# BreakOut-8x8-rev2.net
KiCad netlist of a schematic drawn in EAGLE
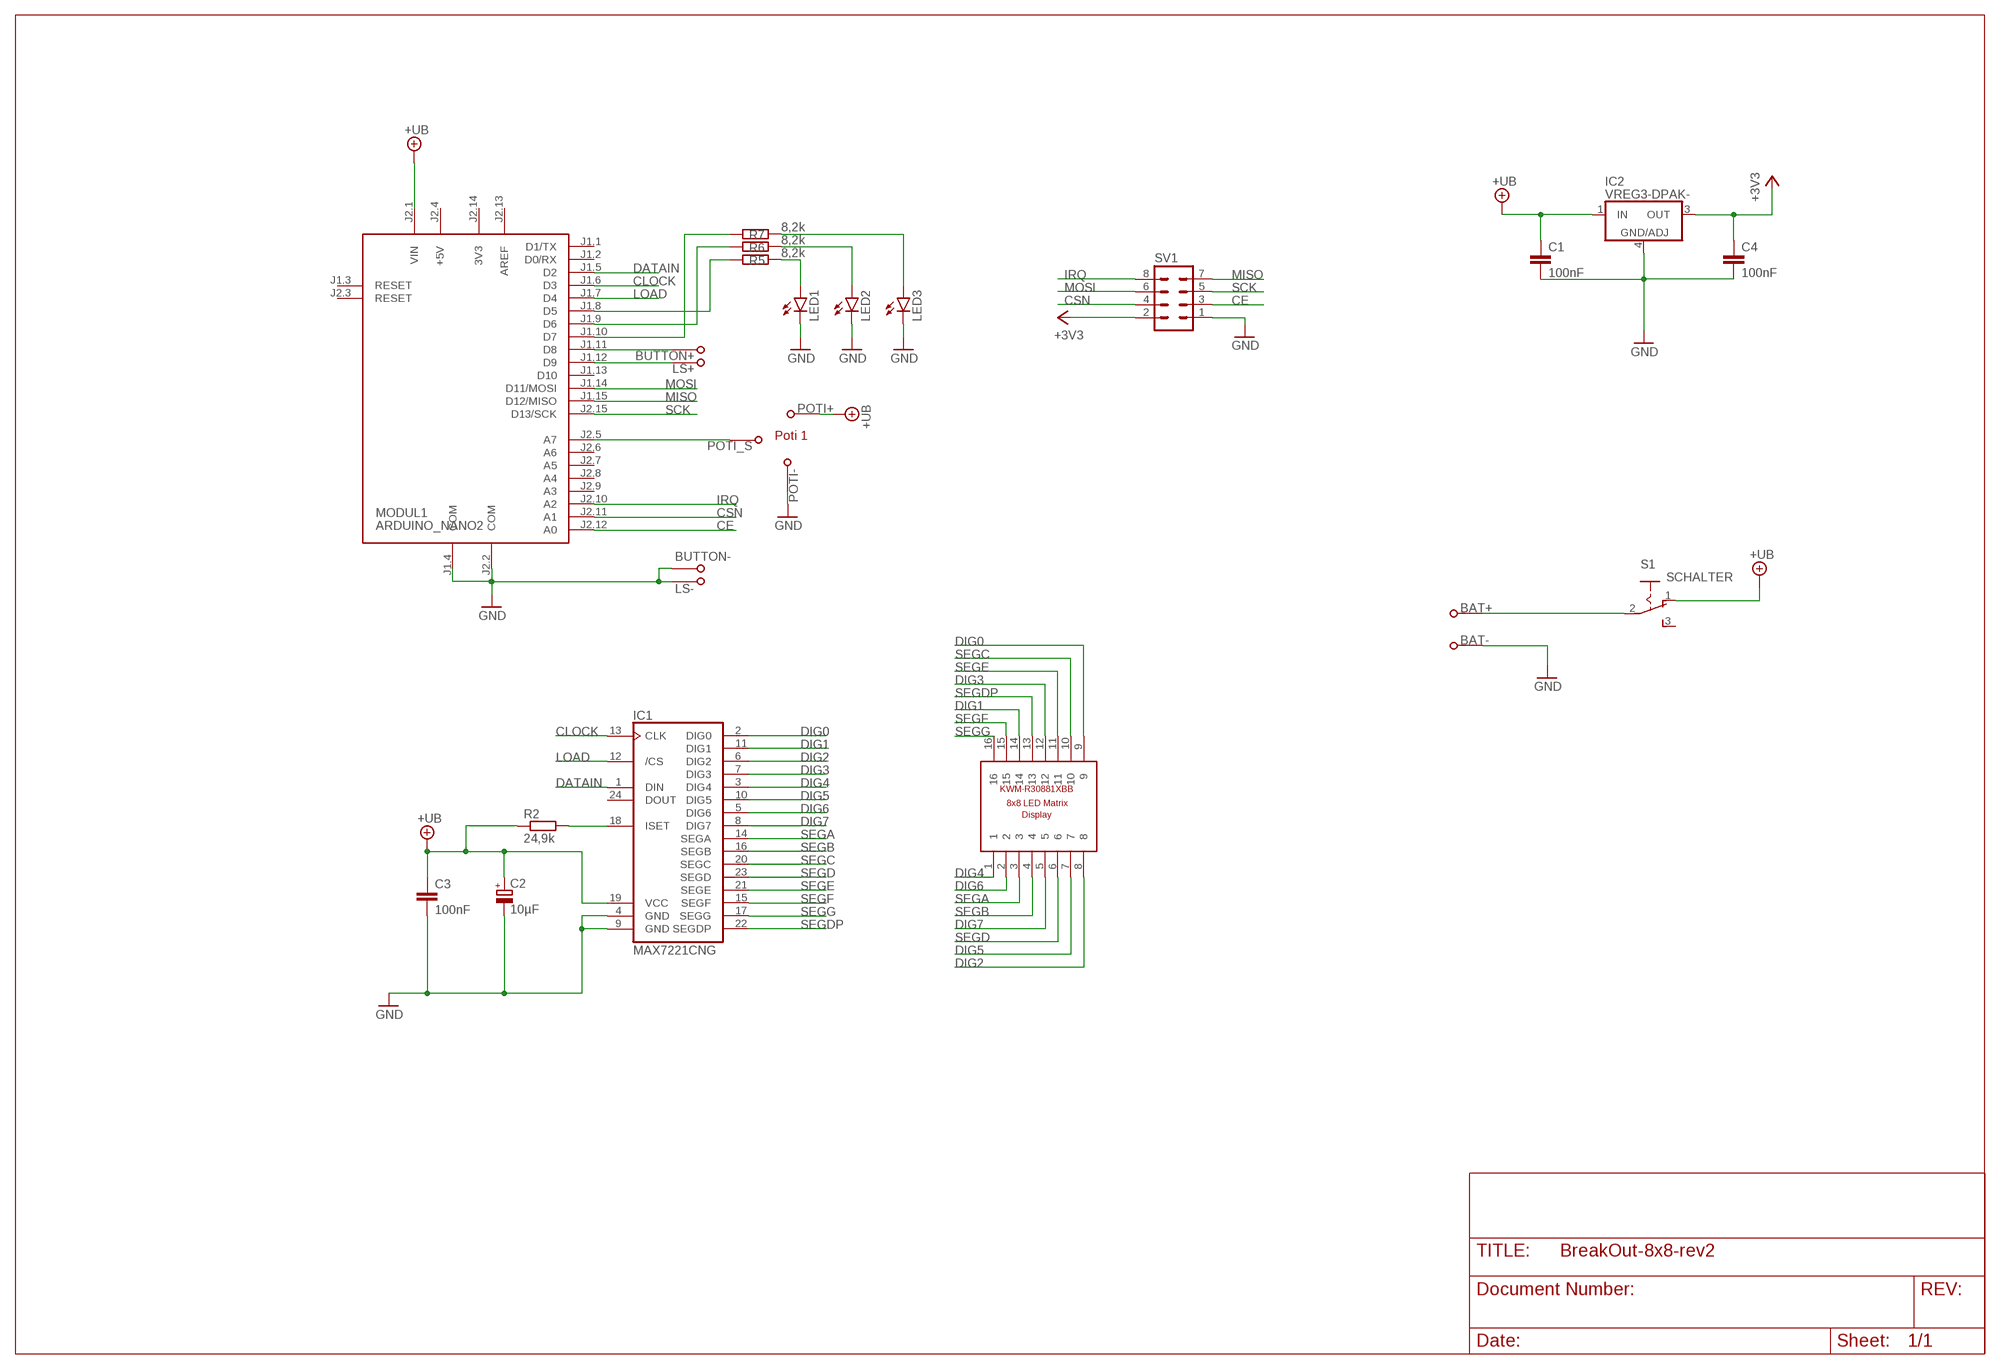
[diagram p0: schematic, sheet 1]

(export (version "E")
  (design (tool "Eeschema 10.0.6"))
  (components
    (comp (ref "BAT+")
      (value "PAD-NVSMD-2X3")
      (footprint "eagle-import:PAD-SO-2X3")
      (libsource (lib "eagle-import") (part "PAD-NVSMD-2X3"))
    )
    (comp (ref "BAT-")
      (value "PAD-NVSMD-2X3")
      (footprint "eagle-import:PAD-SO-2X3")
      (libsource (lib "eagle-import") (part "PAD-NVSMD-2X3"))
    )
    (comp (ref "BUTTON+")
      (value "PAD-NVSMD-2X3")
      (footprint "eagle-import:PAD-SO-2X3")
      (libsource (lib "eagle-import") (part "PAD-NVSMD-2X3"))
    )
    (comp (ref "BUTTON-")
      (value "PAD-NVSMD-2X3")
      (footprint "eagle-import:PAD-SO-2X3")
      (libsource (lib "eagle-import") (part "PAD-NVSMD-2X3"))
    )
    (comp (ref "C1")
      (value "100nF")
      (footprint "eagle-import:C0805")
      (libsource (lib "eagle-import") (part "C-EUC0805"))
    )
    (comp (ref "C2")
      (value "10µF")
      (footprint "eagle-import:C_6032-28R")
      (libsource (lib "eagle-import") (part "CPOL-EUC/6032-28R"))
    )
    (comp (ref "C3")
      (value "100nF")
      (footprint "eagle-import:C0805")
      (libsource (lib "eagle-import") (part "C-EUC0805"))
    )
    (comp (ref "C4")
      (value "100nF")
      (footprint "eagle-import:C0805")
      (libsource (lib "eagle-import") (part "C-EUC0805"))
    )
    (comp (ref "IC1")
      (value "MAX7221CNG")
      (footprint "eagle-import:DIL24-3")
      (libsource (lib "eagle-import") (part "MAX7221NGC"))
    )
    (comp (ref "IC2")
      (value "VREG3-DPAK-")
      (footprint "eagle-import:DPAK")
      (libsource (lib "eagle-import") (part "VREG3-?-DPAK"))
    )
    (comp (ref "LED1")
      (value "LED5MM")
      (footprint "eagle-import:LED5MM")
      (libsource (lib "eagle-import") (part "LED5MM"))
    )
    (comp (ref "LED2")
      (value "LED5MM")
      (footprint "eagle-import:LED5MM")
      (libsource (lib "eagle-import") (part "LED5MM"))
    )
    (comp (ref "LED3")
      (value "LED5MM")
      (footprint "eagle-import:LED5MM")
      (libsource (lib "eagle-import") (part "LED5MM"))
    )
    (comp (ref "LS+")
      (value "PAD-NVSMD-2X3")
      (footprint "eagle-import:PAD-SO-2X3")
      (libsource (lib "eagle-import") (part "PAD-NVSMD-2X3"))
    )
    (comp (ref "LS-")
      (value "PAD-NVSMD-2X3")
      (footprint "eagle-import:PAD-SO-2X3")
      (libsource (lib "eagle-import") (part "PAD-NVSMD-2X3"))
    )
    (comp (ref "MODUL1")
      (value "ARDUINO_NANO2")
      (footprint "eagle-import:ARDUINO_NANO2")
      (libsource (lib "eagle-import") (part "ARDUINO_NANO2"))
    )
    (comp (ref "POTI+")
      (value "PAD-NVSMD-2X3")
      (footprint "eagle-import:PAD-SO-2X3")
      (libsource (lib "eagle-import") (part "PAD-NVSMD-2X3"))
    )
    (comp (ref "POTI-")
      (value "PAD-NVSMD-2X3")
      (footprint "eagle-import:PAD-SO-2X3")
      (libsource (lib "eagle-import") (part "PAD-NVSMD-2X3"))
    )
    (comp (ref "POTI_S")
      (value "PAD-NVSMD-2X3")
      (footprint "eagle-import:PAD-SO-2X3")
      (libsource (lib "eagle-import") (part "PAD-NVSMD-2X3"))
    )
    (comp (ref "R2")
      (value "24,9k")
      (footprint "eagle-import:R0805")
      (libsource (lib "eagle-import") (part "R-EU_R0805"))
    )
    (comp (ref "R5")
      (value "8,2k")
      (footprint "eagle-import:R0805")
      (libsource (lib "eagle-import") (part "R-EU_R0805"))
    )
    (comp (ref "R6")
      (value "8,2k")
      (footprint "eagle-import:R0805")
      (libsource (lib "eagle-import") (part "R-EU_R0805"))
    )
    (comp (ref "R7")
      (value "8,2k")
      (footprint "eagle-import:R0805")
      (libsource (lib "eagle-import") (part "R-EU_R0805"))
    )
    (comp (ref "S1")
      (value "SCHALTER")
      (footprint "eagle-import:255SB")
      (libsource (lib "eagle-import") (part "SCHALTER"))
    )
    (comp (ref "SV1")
      (value "MA04-2")
      (footprint "eagle-import:MA04-2")
      (libsource (lib "eagle-import") (part "MA04-2"))
    )
    (comp (ref "U$1")
      (value "KWM-R30881XBB")
      (footprint "eagle-import:KWM-R30881XBB")
      (libsource (lib "eagle-import") (part "KWM-R30881XBB"))
    )
  )
  (nets
    (net (code "1") (name "+3V3") (class "Default")
      (node (ref "C4") (pin "1") (pinfunction "1_1") (pintype "passive"))
      (node (ref "IC2") (pin "3") (pinfunction "OUT_3") (pintype "passive"))
      (node (ref "SV1") (pin "2") (pinfunction "2_2") (pintype "passive"))
    )
    (net (code "2") (name "+UB") (class "Default")
      (node (ref "C1") (pin "1") (pinfunction "1_1") (pintype "passive"))
      (node (ref "C2") (pin "+") (pinfunction "+_+") (pintype "passive"))
      (node (ref "C3") (pin "1") (pinfunction "1_1") (pintype "passive"))
      (node (ref "IC1") (pin "19") (pinfunction "VCC_19") (pintype "power_in"))
      (node (ref "IC2") (pin "1") (pinfunction "IN_1") (pintype "input"))
      (node (ref "MODUL1") (pin "J2.1") (pinfunction "VIN_J2.1") (pintype "power_in"))
      (node (ref "POTI+") (pin "1") (pinfunction "1_1") (pintype "passive"))
      (node (ref "R2") (pin "1") (pinfunction "1_1") (pintype "passive"))
      (node (ref "S1") (pin "1") (pinfunction "1_1") (pintype "passive"))
    )
    (net (code "3") (name "/+5V") (class "Default")
      (node (ref "MODUL1") (pin "J2.4") (pinfunction "+5V_J2.4") (pintype "power_in"))
    )
    (net (code "4") (name "/3V3") (class "Default")
      (node (ref "MODUL1") (pin "J2.14") (pinfunction "3V3_J2.14") (pintype "power_in"))
    )
    (net (code "5") (name "/AREF") (class "Default")
      (node (ref "MODUL1") (pin "J2.13") (pinfunction "AREF_J2.13") (pintype "power_in"))
    )
    (net (code "6") (name "/CE") (class "Default")
      (node (ref "MODUL1") (pin "J2.12") (pinfunction "A0_J2.12") (pintype "bidirectional"))
      (node (ref "SV1") (pin "3") (pinfunction "3_3") (pintype "passive"))
    )
    (net (code "7") (name "/CLOCK") (class "Default")
      (node (ref "IC1") (pin "13") (pinfunction "CLK_13") (pintype "input"))
      (node (ref "MODUL1") (pin "J1.6") (pinfunction "D3_J1.6") (pintype "bidirectional"))
    )
    (net (code "8") (name "/CSN") (class "Default")
      (node (ref "MODUL1") (pin "J2.11") (pinfunction "A1_J2.11") (pintype "bidirectional"))
      (node (ref "SV1") (pin "4") (pinfunction "4_4") (pintype "passive"))
    )
    (net (code "9") (name "/DATAIN") (class "Default")
      (node (ref "IC1") (pin "1") (pinfunction "DIN_1") (pintype "input"))
      (node (ref "MODUL1") (pin "J1.5") (pinfunction "D2_J1.5") (pintype "bidirectional"))
    )
    (net (code "10") (name "/DIG0") (class "Default")
      (node (ref "IC1") (pin "2") (pinfunction "DIG0_2") (pintype "open_collector"))
      (node (ref "U$1") (pin "9") (pinfunction "9_9") (pintype "bidirectional"))
    )
    (net (code "11") (name "/DIG1") (class "Default")
      (node (ref "IC1") (pin "11") (pinfunction "DIG1_11") (pintype "open_collector"))
      (node (ref "U$1") (pin "14") (pinfunction "14_14") (pintype "bidirectional"))
    )
    (net (code "12") (name "/DIG2") (class "Default")
      (node (ref "IC1") (pin "6") (pinfunction "DIG2_6") (pintype "open_collector"))
      (node (ref "U$1") (pin "8") (pinfunction "8_8") (pintype "bidirectional"))
    )
    (net (code "13") (name "/DIG3") (class "Default")
      (node (ref "IC1") (pin "7") (pinfunction "DIG3_7") (pintype "open_collector"))
      (node (ref "U$1") (pin "12") (pinfunction "12_12") (pintype "bidirectional"))
    )
    (net (code "14") (name "/DIG4") (class "Default")
      (node (ref "IC1") (pin "3") (pinfunction "DIG4_3") (pintype "open_collector"))
      (node (ref "U$1") (pin "1") (pinfunction "1_1") (pintype "bidirectional"))
    )
    (net (code "15") (name "/DIG5") (class "Default")
      (node (ref "IC1") (pin "10") (pinfunction "DIG5_10") (pintype "open_collector"))
      (node (ref "U$1") (pin "7") (pinfunction "7_7") (pintype "bidirectional"))
    )
    (net (code "16") (name "/DIG6") (class "Default")
      (node (ref "IC1") (pin "5") (pinfunction "DIG6_5") (pintype "open_collector"))
      (node (ref "U$1") (pin "2") (pinfunction "2_2") (pintype "bidirectional"))
    )
    (net (code "17") (name "/DIG7") (class "Default")
      (node (ref "IC1") (pin "8") (pinfunction "DIG7_8") (pintype "open_collector"))
      (node (ref "U$1") (pin "5") (pinfunction "5_5") (pintype "bidirectional"))
    )
    (net (code "18") (name "/IRQ") (class "Default")
      (node (ref "MODUL1") (pin "J2.10") (pinfunction "A2_J2.10") (pintype "bidirectional"))
      (node (ref "SV1") (pin "8") (pinfunction "8_8") (pintype "passive"))
    )
    (net (code "19") (name "/LOAD") (class "Default")
      (node (ref "IC1") (pin "12") (pinfunction "/CS_12") (pintype "input"))
      (node (ref "MODUL1") (pin "J1.7") (pinfunction "D4_J1.7") (pintype "bidirectional"))
    )
    (net (code "20") (name "/MISO") (class "Default")
      (node (ref "MODUL1") (pin "J1.15") (pinfunction "D12/MISO_J1.15") (pintype "bidirectional"))
      (node (ref "SV1") (pin "7") (pinfunction "7_7") (pintype "passive"))
    )
    (net (code "21") (name "/MOSI") (class "Default")
      (node (ref "MODUL1") (pin "J1.14") (pinfunction "D11/MOSI_J1.14") (pintype "bidirectional"))
      (node (ref "SV1") (pin "6") (pinfunction "6_6") (pintype "passive"))
    )
    (net (code "22") (name "/SCK") (class "Default")
      (node (ref "MODUL1") (pin "J2.15") (pinfunction "D13/SCK_J2.15") (pintype "bidirectional"))
      (node (ref "SV1") (pin "5") (pinfunction "5_5") (pintype "passive"))
    )
    (net (code "23") (name "/SEGA") (class "Default")
      (node (ref "IC1") (pin "14") (pinfunction "SEGA_14") (pintype "output"))
      (node (ref "U$1") (pin "3") (pinfunction "3_3") (pintype "bidirectional"))
    )
    (net (code "24") (name "/SEGB") (class "Default")
      (node (ref "IC1") (pin "16") (pinfunction "SEGB_16") (pintype "output"))
      (node (ref "U$1") (pin "4") (pinfunction "4_4") (pintype "bidirectional"))
    )
    (net (code "25") (name "/SEGC") (class "Default")
      (node (ref "IC1") (pin "20") (pinfunction "SEGC_20") (pintype "output"))
      (node (ref "U$1") (pin "10") (pinfunction "10_10") (pintype "bidirectional"))
    )
    (net (code "26") (name "/SEGD") (class "Default")
      (node (ref "IC1") (pin "23") (pinfunction "SEGD_23") (pintype "output"))
      (node (ref "U$1") (pin "6") (pinfunction "6_6") (pintype "bidirectional"))
    )
    (net (code "27") (name "/SEGDP") (class "Default")
      (node (ref "IC1") (pin "22") (pinfunction "SEGDP_22") (pintype "output"))
      (node (ref "U$1") (pin "13") (pinfunction "13_13") (pintype "bidirectional"))
    )
    (net (code "28") (name "/SEGE") (class "Default")
      (node (ref "IC1") (pin "21") (pinfunction "SEGE_21") (pintype "output"))
      (node (ref "U$1") (pin "11") (pinfunction "11_11") (pintype "bidirectional"))
    )
    (net (code "29") (name "/SEGF") (class "Default")
      (node (ref "IC1") (pin "15") (pinfunction "SEGF_15") (pintype "output"))
      (node (ref "U$1") (pin "15") (pinfunction "15_15") (pintype "bidirectional"))
    )
    (net (code "30") (name "/SEGG") (class "Default")
      (node (ref "IC1") (pin "17") (pinfunction "SEGG_17") (pintype "output"))
      (node (ref "U$1") (pin "16") (pinfunction "16_16") (pintype "bidirectional"))
    )
    (net (code "31") (name "GND") (class "Default")
      (node (ref "BAT-") (pin "1") (pinfunction "1_1") (pintype "passive"))
      (node (ref "BUTTON-") (pin "1") (pinfunction "1_1") (pintype "passive"))
      (node (ref "C1") (pin "2") (pinfunction "2_2") (pintype "passive"))
      (node (ref "C2") (pin "-") (pinfunction "-_-") (pintype "passive"))
      (node (ref "C3") (pin "2") (pinfunction "2_2") (pintype "passive"))
      (node (ref "C4") (pin "2") (pinfunction "2_2") (pintype "passive"))
      (node (ref "IC1") (pin "4") (pinfunction "GND_4") (pintype "power_in"))
      (node (ref "IC1") (pin "9") (pinfunction "GND_9") (pintype "power_in"))
      (node (ref "IC2") (pin "4") (pinfunction "GND/ADJ_4") (pintype "passive"))
      (node (ref "LED1") (pin "K") (pinfunction "C_K") (pintype "passive"))
      (node (ref "LED2") (pin "K") (pinfunction "C_K") (pintype "passive"))
      (node (ref "LED3") (pin "K") (pinfunction "C_K") (pintype "passive"))
      (node (ref "LS-") (pin "1") (pinfunction "1_1") (pintype "passive"))
      (node (ref "MODUL1") (pin "J1.4") (pinfunction "COM_J1.4") (pintype "power_in"))
      (node (ref "MODUL1") (pin "J2.2") (pinfunction "COM_J2.2") (pintype "power_in"))
      (node (ref "POTI-") (pin "1") (pinfunction "1_1") (pintype "passive"))
      (node (ref "SV1") (pin "1") (pinfunction "1_1") (pintype "passive"))
    )
    (net (code "32") (name "Net-(BAT+-Pad1)") (class "Default")
      (node (ref "BAT+") (pin "1") (pinfunction "1_1") (pintype "passive"))
      (node (ref "S1") (pin "2") (pinfunction "2_2") (pintype "passive"))
    )
    (net (code "33") (name "Net-(IC1-ISET)") (class "Default")
      (node (ref "IC1") (pin "18") (pinfunction "ISET_18") (pintype "input"))
      (node (ref "R2") (pin "2") (pinfunction "2_2") (pintype "passive"))
    )
    (net (code "34") (name "Net-(LED1-PadA)") (class "Default")
      (node (ref "LED1") (pin "A") (pinfunction "A_A") (pintype "passive"))
      (node (ref "R5") (pin "2") (pinfunction "2_2") (pintype "passive"))
    )
    (net (code "35") (name "Net-(LED2-PadA)") (class "Default")
      (node (ref "LED2") (pin "A") (pinfunction "A_A") (pintype "passive"))
      (node (ref "R6") (pin "2") (pinfunction "2_2") (pintype "passive"))
    )
    (net (code "36") (name "Net-(LED3-PadA)") (class "Default")
      (node (ref "LED3") (pin "A") (pinfunction "A_A") (pintype "passive"))
      (node (ref "R7") (pin "2") (pinfunction "2_2") (pintype "passive"))
    )
    (net (code "37") (name "Net-(MODUL1-A7)") (class "Default")
      (node (ref "MODUL1") (pin "J2.5") (pinfunction "A7_J2.5") (pintype "bidirectional"))
      (node (ref "POTI_S") (pin "1") (pinfunction "1_1") (pintype "passive"))
    )
    (net (code "38") (name "Net-(MODUL1-D5)") (class "Default")
      (node (ref "MODUL1") (pin "J1.8") (pinfunction "D5_J1.8") (pintype "bidirectional"))
      (node (ref "R5") (pin "1") (pinfunction "1_1") (pintype "passive"))
    )
    (net (code "39") (name "Net-(MODUL1-D6)") (class "Default")
      (node (ref "MODUL1") (pin "J1.9") (pinfunction "D6_J1.9") (pintype "bidirectional"))
      (node (ref "R6") (pin "1") (pinfunction "1_1") (pintype "passive"))
    )
    (net (code "40") (name "Net-(MODUL1-D7)") (class "Default")
      (node (ref "MODUL1") (pin "J1.10") (pinfunction "D7_J1.10") (pintype "bidirectional"))
      (node (ref "R7") (pin "1") (pinfunction "1_1") (pintype "passive"))
    )
    (net (code "41") (name "Net-(MODUL1-D8)") (class "Default")
      (node (ref "BUTTON+") (pin "1") (pinfunction "1_1") (pintype "passive"))
      (node (ref "MODUL1") (pin "J1.11") (pinfunction "D8_J1.11") (pintype "bidirectional"))
    )
    (net (code "42") (name "Net-(MODUL1-D9)") (class "Default")
      (node (ref "LS+") (pin "1") (pinfunction "1_1") (pintype "passive"))
      (node (ref "MODUL1") (pin "J1.12") (pinfunction "D9_J1.12") (pintype "bidirectional"))
    )
    (net (code "43") (name "unconnected-(IC1-DOUT-Pad24)") (class "Default")
      (node (ref "IC1") (pin "24") (pinfunction "DOUT_24") (pintype "output"))
    )
    (net (code "44") (name "unconnected-(MODUL1-A3-PadJ2.9)") (class "Default")
      (node (ref "MODUL1") (pin "J2.9") (pinfunction "A3_J2.9") (pintype "bidirectional"))
    )
    (net (code "45") (name "unconnected-(MODUL1-A4-PadJ2.8)") (class "Default")
      (node (ref "MODUL1") (pin "J2.8") (pinfunction "A4_J2.8") (pintype "bidirectional"))
    )
    (net (code "46") (name "unconnected-(MODUL1-A5-PadJ2.7)") (class "Default")
      (node (ref "MODUL1") (pin "J2.7") (pinfunction "A5_J2.7") (pintype "bidirectional"))
    )
    (net (code "47") (name "unconnected-(MODUL1-A6-PadJ2.6)") (class "Default")
      (node (ref "MODUL1") (pin "J2.6") (pinfunction "A6_J2.6") (pintype "bidirectional"))
    )
    (net (code "48") (name "unconnected-(MODUL1-D0{slash}RX-PadJ1.2)") (class "Default")
      (node (ref "MODUL1") (pin "J1.2") (pinfunction "D0/RX_J1.2") (pintype "bidirectional"))
    )
    (net (code "49") (name "unconnected-(MODUL1-D1{slash}TX-PadJ1.1)") (class "Default")
      (node (ref "MODUL1") (pin "J1.1") (pinfunction "D1/TX_J1.1") (pintype "bidirectional"))
    )
    (net (code "50") (name "unconnected-(MODUL1-D10-PadJ1.13)") (class "Default")
      (node (ref "MODUL1") (pin "J1.13") (pinfunction "D10_J1.13") (pintype "bidirectional"))
    )
    (net (code "51") (name "unconnected-(MODUL1-RESET-PadJ1.3)") (class "Default")
      (node (ref "MODUL1") (pin "J1.3") (pinfunction "RESET_J1.3") (pintype "bidirectional"))
    )
    (net (code "52") (name "unconnected-(MODUL1-RESET-PadJ2.3)") (class "Default")
      (node (ref "MODUL1") (pin "J2.3") (pinfunction "RESET_J2.3") (pintype "bidirectional"))
    )
    (net (code "53") (name "unconnected-(S1-Pad3)") (class "Default")
      (node (ref "S1") (pin "3") (pinfunction "3_3") (pintype "passive"))
    )
  )
)
